# Foozle2650.net
KiCad netlist of a schematic drawn in EAGLE
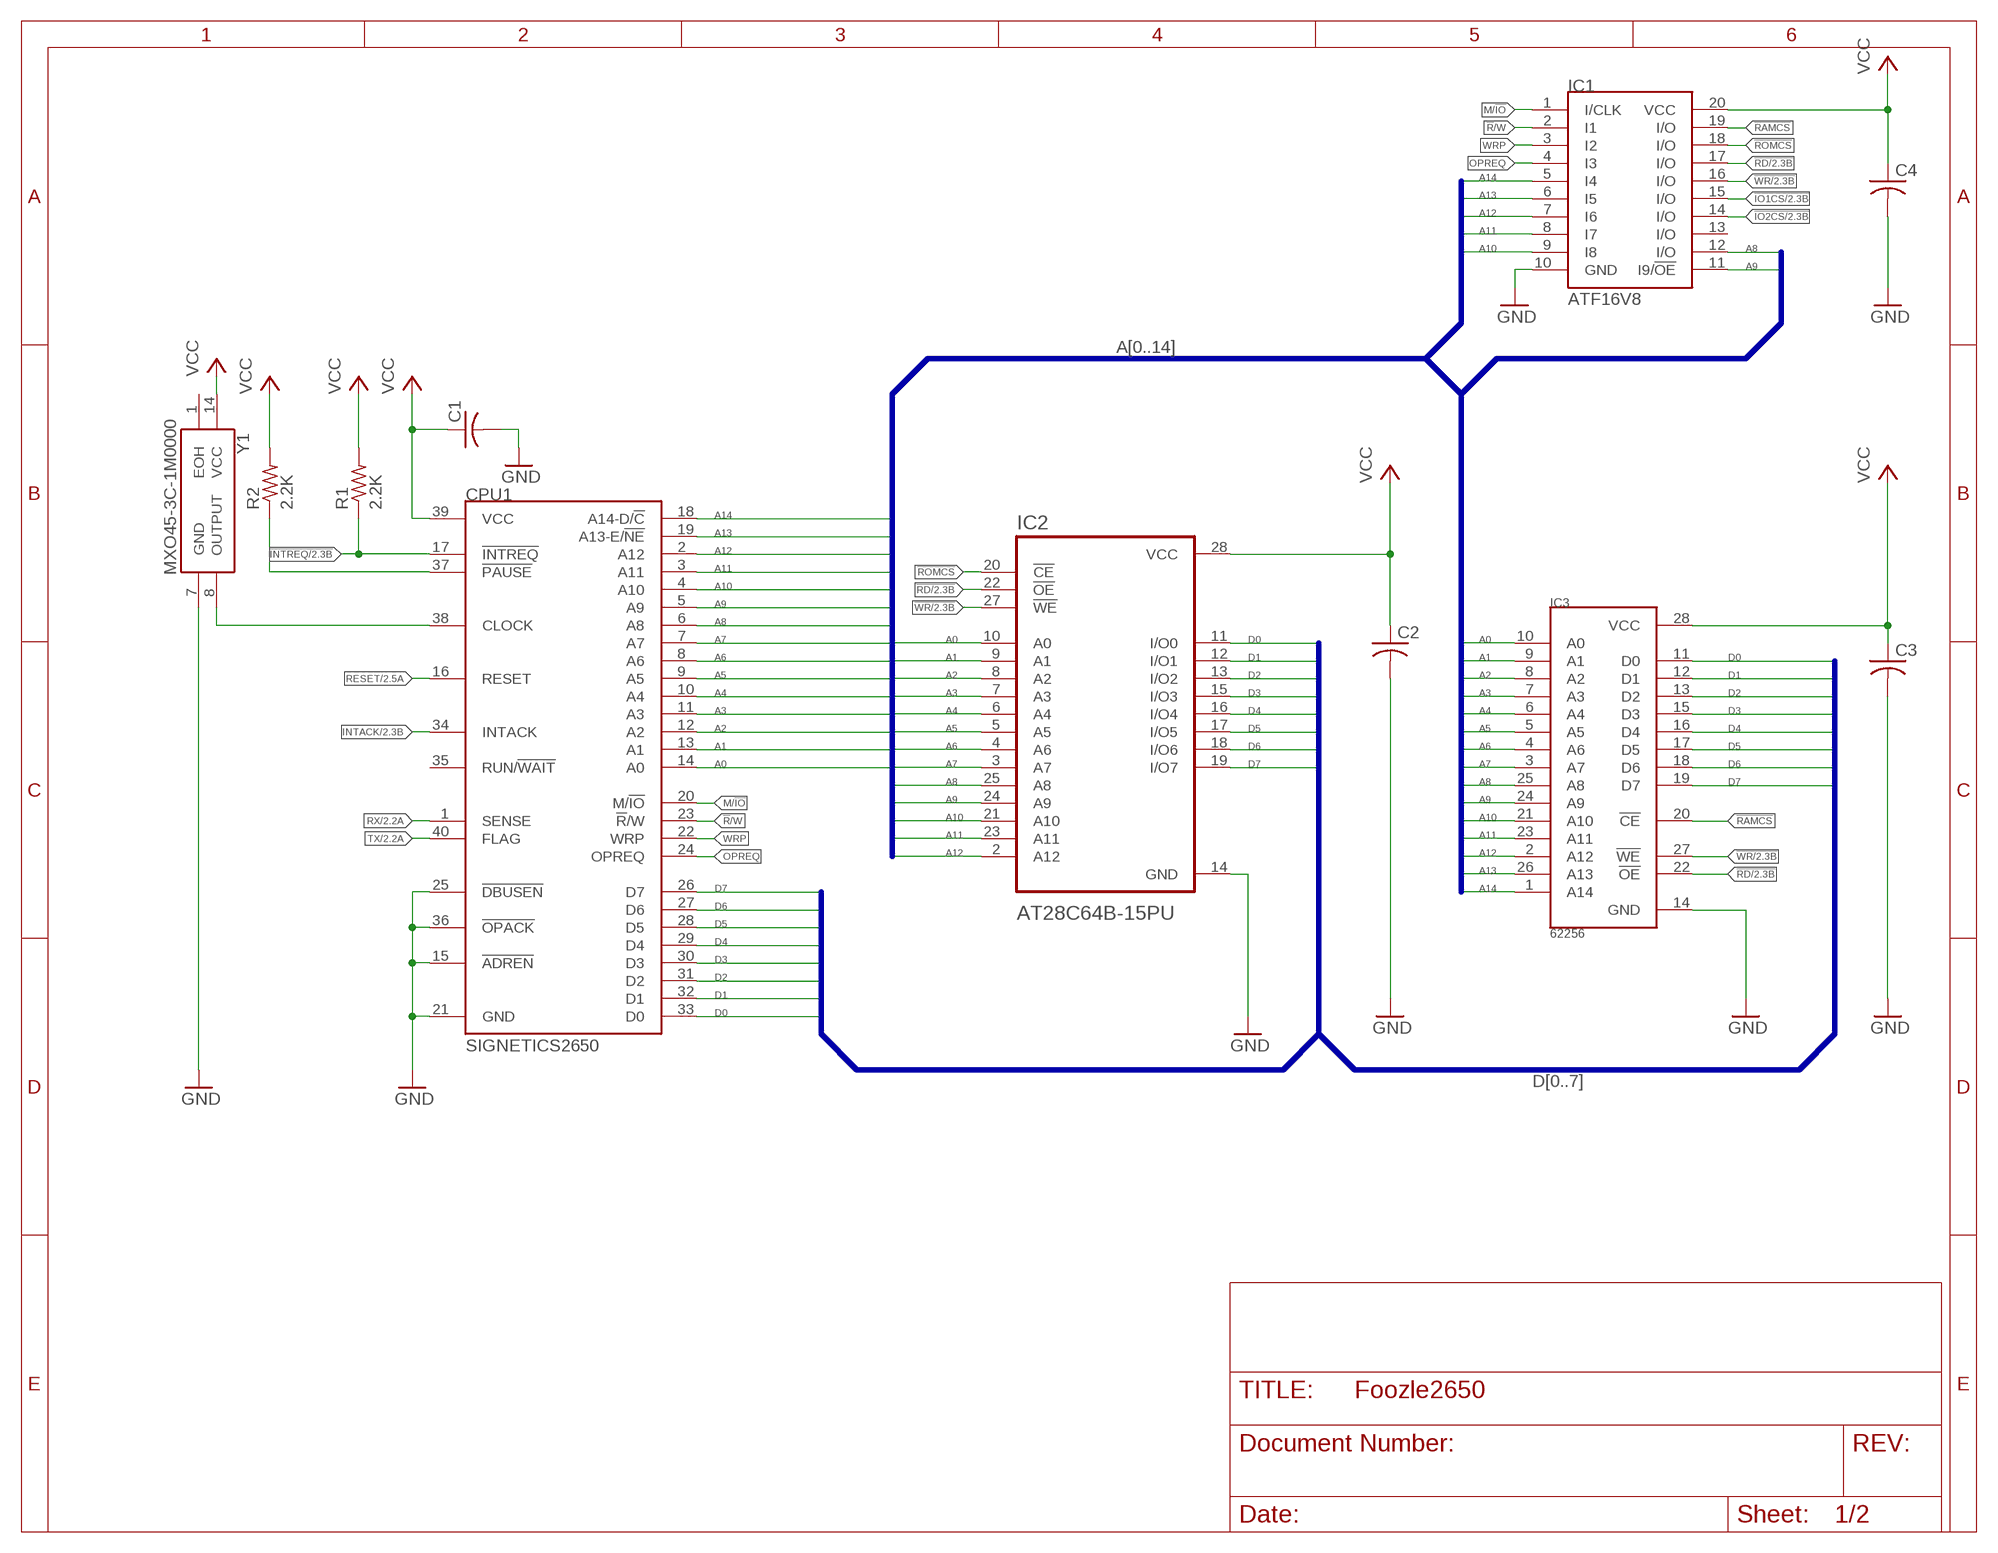
[diagram p0: schematic, sheet 1]
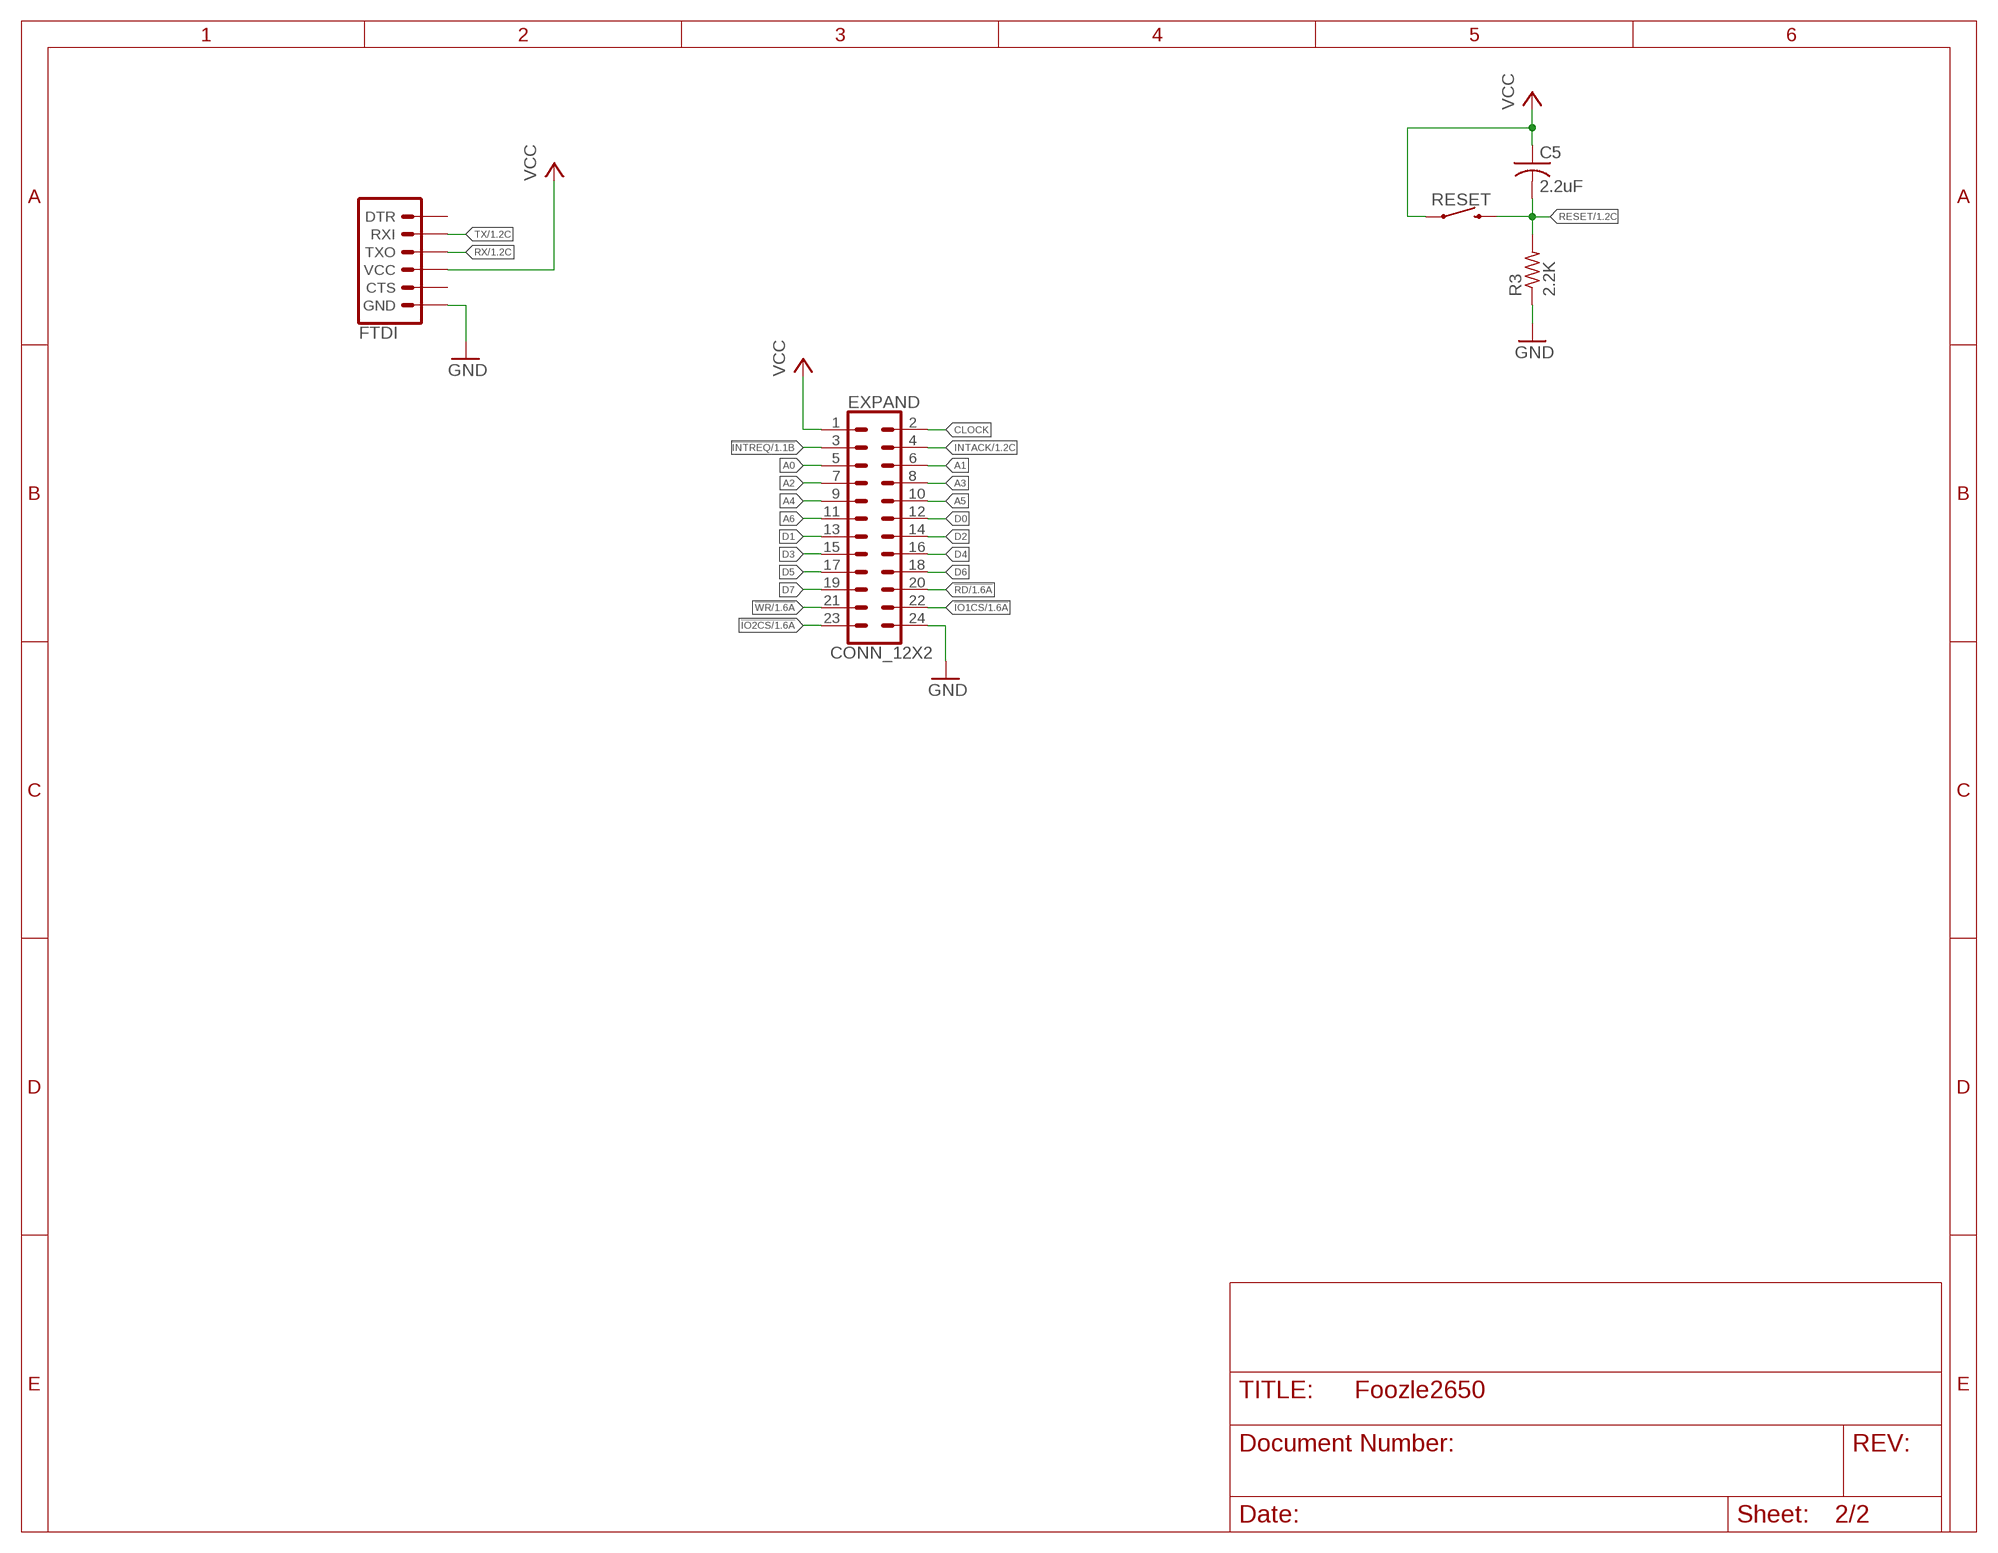
[diagram p1: schematic, sheet 2]

(export (version "E")
  (design (tool "Eeschema 10.0.6"))
  (components
    (comp (ref "C5")
      (value "2.2uF")
      (footprint "eagle-import:C025-024X044")
      (libsource (lib "eagle-import") (part "C-US025-024X044"))
    )
    (comp (ref "EXPAND")
      (value "CONN_12X2")
      (footprint "eagle-import:2X12")
      (libsource (lib "eagle-import") (part "CONN_12X2"))
    )
    (comp (ref "FTDI")
      (value "6_PIN_SERIAL_TARGETLONGPADS")
      (footprint "eagle-import:1X06_LONGPADS")
      (libsource (lib "eagle-import") (part "6_PIN_SERIAL_TARGETLONGPADS"))
    )
    (comp (ref "R3")
      (value "2.2K")
      (footprint "eagle-import:0204_7")
      (libsource (lib "eagle-import") (part "R-US_0204/7"))
    )
    (comp (ref "RESET")
      (value "MOMENTARY-SWITCH-SPST-PTH-6.0MM")
      (footprint "eagle-import:TACTILE_SWITCH_PTH_6.0MM")
      (libsource (lib "eagle-import") (part "MOMENTARY-SWITCH-SPST-PTH-6.0MM"))
    )
    (comp (ref "C1")
      (value "C-US025-024X044")
      (footprint "eagle-import:C025-024X044")
      (libsource (lib "eagle-import") (part "C-US025-024X044"))
    )
    (comp (ref "C2")
      (value "C-US025-024X044")
      (footprint "eagle-import:C025-024X044")
      (libsource (lib "eagle-import") (part "C-US025-024X044"))
    )
    (comp (ref "C3")
      (value "C-US025-024X044")
      (footprint "eagle-import:C025-024X044")
      (libsource (lib "eagle-import") (part "C-US025-024X044"))
    )
    (comp (ref "C4")
      (value "C-US025-024X044")
      (footprint "eagle-import:C025-024X044")
      (libsource (lib "eagle-import") (part "C-US025-024X044"))
    )
    (comp (ref "CPU1")
      (value "SIGNETICS2650")
      (footprint "eagle-import:DIL40")
      (libsource (lib "eagle-import") (part "SIGNETICS2650"))
    )
    (comp (ref "IC1")
      (value "ATF16V8")
      (footprint "eagle-import:DIL20")
      (libsource (lib "eagle-import") (part "ATF16V8"))
    )
    (comp (ref "IC2")
      (value "AT28C64B-15PU")
      (footprint "eagle-import:DIP1555W45P254L3733H482Q28")
      (fields (field (name "MF") "Microchip Technology"))
      (libsource (lib "eagle-import") (part "AT28C64B-15PU"))
    )
    (comp (ref "IC3")
      (value "62256")
      (footprint "eagle-import:DIP-28_600MIL")
      (libsource (lib "eagle-import") (part "62256"))
    )
    (comp (ref "R1")
      (value "2.2K")
      (footprint "eagle-import:0204_7")
      (libsource (lib "eagle-import") (part "R-US_0204/7"))
    )
    (comp (ref "R2")
      (value "2.2K")
      (footprint "eagle-import:0204_7")
      (libsource (lib "eagle-import") (part "R-US_0204/7"))
    )
    (comp (ref "Y1")
      (value "MXO45-3C-1M0000")
      (footprint "eagle-import:MXO453C1M0000")
      (fields (field (name "MOUSER_PART_NUMBER") "774-MXO45-3C-1.0"))
      (libsource (lib "eagle-import") (part "MXO45-3C-1M0000"))
    )
  )
  (nets
    (net (code "3") (name "A0") (class "Default")
      (node (ref "CPU1") (pin "14") (pinfunction "A0_14") (pintype "bidirectional"))
      (node (ref "EXPAND") (pin "5") (pinfunction "5_5") (pintype "passive"))
      (node (ref "IC2") (pin "10") (pinfunction "A0_10") (pintype "input"))
      (node (ref "IC3") (pin "10") (pinfunction "A0_10") (pintype "bidirectional"))
    )
    (net (code "4") (name "A1") (class "Default")
      (node (ref "CPU1") (pin "13") (pinfunction "A1_13") (pintype "bidirectional"))
      (node (ref "EXPAND") (pin "6") (pinfunction "6_6") (pintype "passive"))
      (node (ref "IC2") (pin "9") (pinfunction "A1_9") (pintype "input"))
      (node (ref "IC3") (pin "9") (pinfunction "A1_9") (pintype "bidirectional"))
    )
    (net (code "5") (name "A2") (class "Default")
      (node (ref "CPU1") (pin "12") (pinfunction "A2_12") (pintype "bidirectional"))
      (node (ref "EXPAND") (pin "7") (pinfunction "7_7") (pintype "passive"))
      (node (ref "IC2") (pin "8") (pinfunction "A2_8") (pintype "input"))
      (node (ref "IC3") (pin "8") (pinfunction "A2_8") (pintype "bidirectional"))
    )
    (net (code "6") (name "A3") (class "Default")
      (node (ref "CPU1") (pin "11") (pinfunction "A3_11") (pintype "bidirectional"))
      (node (ref "EXPAND") (pin "8") (pinfunction "8_8") (pintype "passive"))
      (node (ref "IC2") (pin "7") (pinfunction "A3_7") (pintype "input"))
      (node (ref "IC3") (pin "7") (pinfunction "A3_7") (pintype "bidirectional"))
    )
    (net (code "7") (name "A4") (class "Default")
      (node (ref "CPU1") (pin "10") (pinfunction "A4_10") (pintype "bidirectional"))
      (node (ref "EXPAND") (pin "9") (pinfunction "9_9") (pintype "passive"))
      (node (ref "IC2") (pin "6") (pinfunction "A4_6") (pintype "input"))
      (node (ref "IC3") (pin "6") (pinfunction "A4_6") (pintype "bidirectional"))
    )
    (net (code "8") (name "A5") (class "Default")
      (node (ref "CPU1") (pin "9") (pinfunction "A5_9") (pintype "bidirectional"))
      (node (ref "EXPAND") (pin "10") (pinfunction "10_10") (pintype "passive"))
      (node (ref "IC2") (pin "5") (pinfunction "A5_5") (pintype "input"))
      (node (ref "IC3") (pin "5") (pinfunction "A5_5") (pintype "bidirectional"))
    )
    (net (code "9") (name "A6") (class "Default")
      (node (ref "CPU1") (pin "8") (pinfunction "A6_8") (pintype "bidirectional"))
      (node (ref "EXPAND") (pin "11") (pinfunction "11_11") (pintype "passive"))
      (node (ref "IC2") (pin "4") (pinfunction "A6_4") (pintype "input"))
      (node (ref "IC3") (pin "4") (pinfunction "A6_4") (pintype "bidirectional"))
    )
    (net (code "10") (name "A7") (class "Default")
      (node (ref "CPU1") (pin "7") (pinfunction "A7_7") (pintype "bidirectional"))
      (node (ref "IC2") (pin "3") (pinfunction "A7_3") (pintype "input"))
      (node (ref "IC3") (pin "3") (pinfunction "A7_3") (pintype "bidirectional"))
    )
    (net (code "11") (name "A8") (class "Default")
      (node (ref "CPU1") (pin "6") (pinfunction "A8_6") (pintype "bidirectional"))
      (node (ref "IC1") (pin "12") (pinfunction "I/O_12") (pintype "bidirectional"))
      (node (ref "IC2") (pin "25") (pinfunction "A8_25") (pintype "input"))
      (node (ref "IC3") (pin "25") (pinfunction "A8_25") (pintype "bidirectional"))
    )
    (net (code "12") (name "A9") (class "Default")
      (node (ref "CPU1") (pin "5") (pinfunction "A9_5") (pintype "bidirectional"))
      (node (ref "IC1") (pin "11") (pinfunction "I9/~{OE}_11") (pintype "bidirectional"))
      (node (ref "IC2") (pin "24") (pinfunction "A9_24") (pintype "input"))
      (node (ref "IC3") (pin "24") (pinfunction "A9_24") (pintype "bidirectional"))
    )
    (net (code "13") (name "A10") (class "Default")
      (node (ref "CPU1") (pin "4") (pinfunction "A10_4") (pintype "bidirectional"))
      (node (ref "IC1") (pin "9") (pinfunction "I8_9") (pintype "bidirectional"))
      (node (ref "IC2") (pin "21") (pinfunction "A10_21") (pintype "input"))
      (node (ref "IC3") (pin "21") (pinfunction "A10_21") (pintype "bidirectional"))
    )
    (net (code "14") (name "A11") (class "Default")
      (node (ref "CPU1") (pin "3") (pinfunction "A11_3") (pintype "bidirectional"))
      (node (ref "IC1") (pin "8") (pinfunction "I7_8") (pintype "bidirectional"))
      (node (ref "IC2") (pin "23") (pinfunction "A11_23") (pintype "input"))
      (node (ref "IC3") (pin "23") (pinfunction "A11_23") (pintype "bidirectional"))
    )
    (net (code "15") (name "A12") (class "Default")
      (node (ref "CPU1") (pin "2") (pinfunction "A12_2") (pintype "bidirectional"))
      (node (ref "IC1") (pin "7") (pinfunction "I6_7") (pintype "bidirectional"))
      (node (ref "IC2") (pin "2") (pinfunction "A12_2") (pintype "input"))
      (node (ref "IC3") (pin "2") (pinfunction "A12_2") (pintype "bidirectional"))
    )
    (net (code "16") (name "A13") (class "Default")
      (node (ref "CPU1") (pin "19") (pinfunction "A13-E/~{NE}_19") (pintype "bidirectional"))
      (node (ref "IC1") (pin "6") (pinfunction "I5_6") (pintype "bidirectional"))
      (node (ref "IC3") (pin "26") (pinfunction "A13_26") (pintype "bidirectional"))
    )
    (net (code "17") (name "A14") (class "Default")
      (node (ref "CPU1") (pin "18") (pinfunction "A14-D/~{C}_18") (pintype "bidirectional"))
      (node (ref "IC1") (pin "5") (pinfunction "I4_5") (pintype "bidirectional"))
      (node (ref "IC3") (pin "1") (pinfunction "A14_1") (pintype "bidirectional"))
    )
    (net (code "18") (name "CLOCK") (class "Default")
      (node (ref "CPU1") (pin "38") (pinfunction "CLOCK_38") (pintype "bidirectional"))
      (node (ref "EXPAND") (pin "2") (pinfunction "2_2") (pintype "passive"))
      (node (ref "Y1") (pin "8") (pinfunction "OUTPUT_8") (pintype "bidirectional"))
    )
    (net (code "19") (name "D0") (class "Default")
      (node (ref "CPU1") (pin "33") (pinfunction "D0_33") (pintype "bidirectional"))
      (node (ref "EXPAND") (pin "12") (pinfunction "12_12") (pintype "passive"))
      (node (ref "IC2") (pin "11") (pinfunction "I/O0_11") (pintype "bidirectional"))
      (node (ref "IC3") (pin "11") (pinfunction "D0_11") (pintype "bidirectional"))
    )
    (net (code "20") (name "D1") (class "Default")
      (node (ref "CPU1") (pin "32") (pinfunction "D1_32") (pintype "bidirectional"))
      (node (ref "EXPAND") (pin "13") (pinfunction "13_13") (pintype "passive"))
      (node (ref "IC2") (pin "12") (pinfunction "I/O1_12") (pintype "bidirectional"))
      (node (ref "IC3") (pin "12") (pinfunction "D1_12") (pintype "bidirectional"))
    )
    (net (code "21") (name "D2") (class "Default")
      (node (ref "CPU1") (pin "31") (pinfunction "D2_31") (pintype "bidirectional"))
      (node (ref "EXPAND") (pin "14") (pinfunction "14_14") (pintype "passive"))
      (node (ref "IC2") (pin "13") (pinfunction "I/O2_13") (pintype "bidirectional"))
      (node (ref "IC3") (pin "13") (pinfunction "D2_13") (pintype "bidirectional"))
    )
    (net (code "22") (name "D3") (class "Default")
      (node (ref "CPU1") (pin "30") (pinfunction "D3_30") (pintype "bidirectional"))
      (node (ref "EXPAND") (pin "15") (pinfunction "15_15") (pintype "passive"))
      (node (ref "IC2") (pin "15") (pinfunction "I/O3_15") (pintype "bidirectional"))
      (node (ref "IC3") (pin "15") (pinfunction "D3_15") (pintype "bidirectional"))
    )
    (net (code "23") (name "D4") (class "Default")
      (node (ref "CPU1") (pin "29") (pinfunction "D4_29") (pintype "bidirectional"))
      (node (ref "EXPAND") (pin "16") (pinfunction "16_16") (pintype "passive"))
      (node (ref "IC2") (pin "16") (pinfunction "I/O4_16") (pintype "bidirectional"))
      (node (ref "IC3") (pin "16") (pinfunction "D4_16") (pintype "bidirectional"))
    )
    (net (code "24") (name "D5") (class "Default")
      (node (ref "CPU1") (pin "28") (pinfunction "D5_28") (pintype "bidirectional"))
      (node (ref "EXPAND") (pin "17") (pinfunction "17_17") (pintype "passive"))
      (node (ref "IC2") (pin "17") (pinfunction "I/O5_17") (pintype "bidirectional"))
      (node (ref "IC3") (pin "17") (pinfunction "D5_17") (pintype "bidirectional"))
    )
    (net (code "25") (name "D6") (class "Default")
      (node (ref "CPU1") (pin "27") (pinfunction "D6_27") (pintype "bidirectional"))
      (node (ref "EXPAND") (pin "18") (pinfunction "18_18") (pintype "passive"))
      (node (ref "IC2") (pin "18") (pinfunction "I/O6_18") (pintype "bidirectional"))
      (node (ref "IC3") (pin "18") (pinfunction "D6_18") (pintype "bidirectional"))
    )
    (net (code "26") (name "D7") (class "Default")
      (node (ref "CPU1") (pin "26") (pinfunction "D7_26") (pintype "bidirectional"))
      (node (ref "EXPAND") (pin "19") (pinfunction "19_19") (pintype "passive"))
      (node (ref "IC2") (pin "19") (pinfunction "I/O7_19") (pintype "bidirectional"))
      (node (ref "IC3") (pin "19") (pinfunction "D7_19") (pintype "bidirectional"))
    )
    (net (code "27") (name "GND") (class "Default")
      (node (ref "C1") (pin "2") (pinfunction "2_2") (pintype "passive"))
      (node (ref "C2") (pin "2") (pinfunction "2_2") (pintype "passive"))
      (node (ref "C3") (pin "2") (pinfunction "2_2") (pintype "passive"))
      (node (ref "C4") (pin "2") (pinfunction "2_2") (pintype "passive"))
      (node (ref "CPU1") (pin "15") (pinfunction "~{ADREN}_15") (pintype "bidirectional"))
      (node (ref "CPU1") (pin "21") (pinfunction "GND_21") (pintype "bidirectional"))
      (node (ref "CPU1") (pin "25") (pinfunction "~{DBUSEN}_25") (pintype "bidirectional"))
      (node (ref "CPU1") (pin "36") (pinfunction "~{OPACK}_36") (pintype "bidirectional"))
      (node (ref "EXPAND") (pin "24") (pinfunction "24_24") (pintype "passive"))
      (node (ref "FTDI") (pin "6") (pinfunction "GND_6") (pintype "passive"))
      (node (ref "IC1") (pin "10") (pinfunction "GND_10") (pintype "bidirectional"))
      (node (ref "IC2") (pin "14") (pinfunction "GND_14") (pintype "power_in"))
      (node (ref "IC3") (pin "14") (pinfunction "GND_14") (pintype "bidirectional"))
      (node (ref "R3") (pin "1") (pinfunction "1_1") (pintype "passive"))
      (node (ref "Y1") (pin "7") (pinfunction "GND_7") (pintype "bidirectional"))
    )
    (net (code "28") (name "INTACK") (class "Default")
      (node (ref "CPU1") (pin "34") (pinfunction "INTACK_34") (pintype "bidirectional"))
      (node (ref "EXPAND") (pin "4") (pinfunction "4_4") (pintype "passive"))
    )
    (net (code "29") (name "M{slash}~{IO}") (class "Default")
      (node (ref "CPU1") (pin "20") (pinfunction "M/~{IO}_20") (pintype "bidirectional"))
      (node (ref "IC1") (pin "1") (pinfunction "I/CLK_1") (pintype "bidirectional"))
    )
    (net (code "30") (name "Net-(CPU1-~{PAUSE})") (class "Default")
      (node (ref "CPU1") (pin "37") (pinfunction "~{PAUSE}_37") (pintype "bidirectional"))
      (node (ref "R2") (pin "1") (pinfunction "1_1") (pintype "passive"))
    )
    (net (code "31") (name "OPREQ") (class "Default")
      (node (ref "CPU1") (pin "24") (pinfunction "OPREQ_24") (pintype "bidirectional"))
      (node (ref "IC1") (pin "4") (pinfunction "I3_4") (pintype "bidirectional"))
    )
    (net (code "32") (name "RESET") (class "Default")
      (node (ref "C5") (pin "2") (pinfunction "2_2") (pintype "passive"))
      (node (ref "CPU1") (pin "16") (pinfunction "RESET_16") (pintype "bidirectional"))
      (node (ref "R3") (pin "2") (pinfunction "2_2") (pintype "passive"))
      (node (ref "RESET") (pin "3") (pinfunction "2_3") (pintype "passive"))
    )
    (net (code "33") (name "RX") (class "Default")
      (node (ref "CPU1") (pin "1") (pinfunction "SENSE_1") (pintype "bidirectional"))
      (node (ref "FTDI") (pin "3") (pinfunction "TXO_3") (pintype "passive"))
    )
    (net (code "34") (name "TX") (class "Default")
      (node (ref "CPU1") (pin "40") (pinfunction "FLAG_40") (pintype "bidirectional"))
      (node (ref "FTDI") (pin "2") (pinfunction "RXI_2") (pintype "passive"))
    )
    (net (code "35") (name "VCC") (class "Default")
      (node (ref "C1") (pin "1") (pinfunction "1_1") (pintype "passive"))
      (node (ref "C2") (pin "1") (pinfunction "1_1") (pintype "passive"))
      (node (ref "C3") (pin "1") (pinfunction "1_1") (pintype "passive"))
      (node (ref "C4") (pin "1") (pinfunction "1_1") (pintype "passive"))
      (node (ref "C5") (pin "1") (pinfunction "1_1") (pintype "passive"))
      (node (ref "CPU1") (pin "39") (pinfunction "VCC_39") (pintype "bidirectional"))
      (node (ref "EXPAND") (pin "1") (pinfunction "1_1") (pintype "passive"))
      (node (ref "FTDI") (pin "4") (pinfunction "VCC_4") (pintype "passive"))
      (node (ref "IC1") (pin "20") (pinfunction "VCC_20") (pintype "bidirectional"))
      (node (ref "IC2") (pin "28") (pinfunction "VCC_28") (pintype "power_in"))
      (node (ref "IC3") (pin "28") (pinfunction "VCC_28") (pintype "bidirectional"))
      (node (ref "R1") (pin "2") (pinfunction "2_2") (pintype "passive"))
      (node (ref "R2") (pin "2") (pinfunction "2_2") (pintype "passive"))
      (node (ref "RESET") (pin "1") (pinfunction "1_1") (pintype "passive"))
      (node (ref "Y1") (pin "14") (pinfunction "VCC_14") (pintype "bidirectional"))
    )
    (net (code "36") (name "WRP") (class "Default")
      (node (ref "CPU1") (pin "22") (pinfunction "WRP_22") (pintype "bidirectional"))
      (node (ref "IC1") (pin "3") (pinfunction "I2_3") (pintype "bidirectional"))
    )
    (net (code "37") (name "unconnected-(CPU1-RUN{slash}~{WAIT}-Pad35)") (class "Default")
      (node (ref "CPU1") (pin "35") (pinfunction "RUN/~{WAIT}_35") (pintype "bidirectional"))
    )
    (net (code "38") (name "unconnected-(FTDI-CTS-Pad5)") (class "Default")
      (node (ref "FTDI") (pin "5") (pinfunction "CTS_5") (pintype "passive"))
    )
    (net (code "39") (name "unconnected-(FTDI-DTR-Pad1)") (class "Default")
      (node (ref "FTDI") (pin "1") (pinfunction "DTR_1") (pintype "passive"))
    )
    (net (code "40") (name "unconnected-(IC1-I{slash}O-Pad13)") (class "Default")
      (node (ref "IC1") (pin "13") (pinfunction "I/O_13") (pintype "bidirectional"))
    )
    (net (code "41") (name "unconnected-(Y1-EOH-Pad1)") (class "Default")
      (node (ref "Y1") (pin "1") (pinfunction "EOH_1") (pintype "bidirectional"))
    )
    (net (code "42") (name "~{INTREQ}") (class "Default")
      (node (ref "CPU1") (pin "17") (pinfunction "~{INTREQ}_17") (pintype "bidirectional"))
      (node (ref "EXPAND") (pin "3") (pinfunction "3_3") (pintype "passive"))
      (node (ref "R1") (pin "1") (pinfunction "1_1") (pintype "passive"))
    )
    (net (code "43") (name "~{IO1CS}") (class "Default")
      (node (ref "EXPAND") (pin "22") (pinfunction "22_22") (pintype "passive"))
      (node (ref "IC1") (pin "15") (pinfunction "I/O_15") (pintype "bidirectional"))
    )
    (net (code "44") (name "~{IO2CS}") (class "Default")
      (node (ref "EXPAND") (pin "23") (pinfunction "23_23") (pintype "passive"))
      (node (ref "IC1") (pin "14") (pinfunction "I/O_14") (pintype "bidirectional"))
    )
    (net (code "45") (name "~{RAMCS}") (class "Default")
      (node (ref "IC1") (pin "19") (pinfunction "I/O_19") (pintype "bidirectional"))
      (node (ref "IC3") (pin "20") (pinfunction "~{CE}_20") (pintype "bidirectional"))
    )
    (net (code "46") (name "~{RD}") (class "Default")
      (node (ref "EXPAND") (pin "20") (pinfunction "20_20") (pintype "passive"))
      (node (ref "IC1") (pin "17") (pinfunction "I/O_17") (pintype "bidirectional"))
      (node (ref "IC2") (pin "22") (pinfunction "~{OE}_22") (pintype "input"))
      (node (ref "IC3") (pin "22") (pinfunction "~{OE}_22") (pintype "bidirectional"))
    )
    (net (code "47") (name "~{ROMCS}") (class "Default")
      (node (ref "IC1") (pin "18") (pinfunction "I/O_18") (pintype "bidirectional"))
      (node (ref "IC2") (pin "20") (pinfunction "~{CE}_20") (pintype "input"))
    )
    (net (code "48") (name "~{R}{slash}W") (class "Default")
      (node (ref "CPU1") (pin "23") (pinfunction "~{R}/W_23") (pintype "bidirectional"))
      (node (ref "IC1") (pin "2") (pinfunction "I1_2") (pintype "bidirectional"))
    )
    (net (code "49") (name "~{WR}") (class "Default")
      (node (ref "EXPAND") (pin "21") (pinfunction "21_21") (pintype "passive"))
      (node (ref "IC1") (pin "16") (pinfunction "I/O_16") (pintype "bidirectional"))
      (node (ref "IC2") (pin "27") (pinfunction "~{WE}_27") (pintype "input"))
      (node (ref "IC3") (pin "27") (pinfunction "~{WE}_27") (pintype "bidirectional"))
    )
  )
)
